# PowerDeliveryBoard.net
KiCad netlist of a schematic drawn in EAGLE
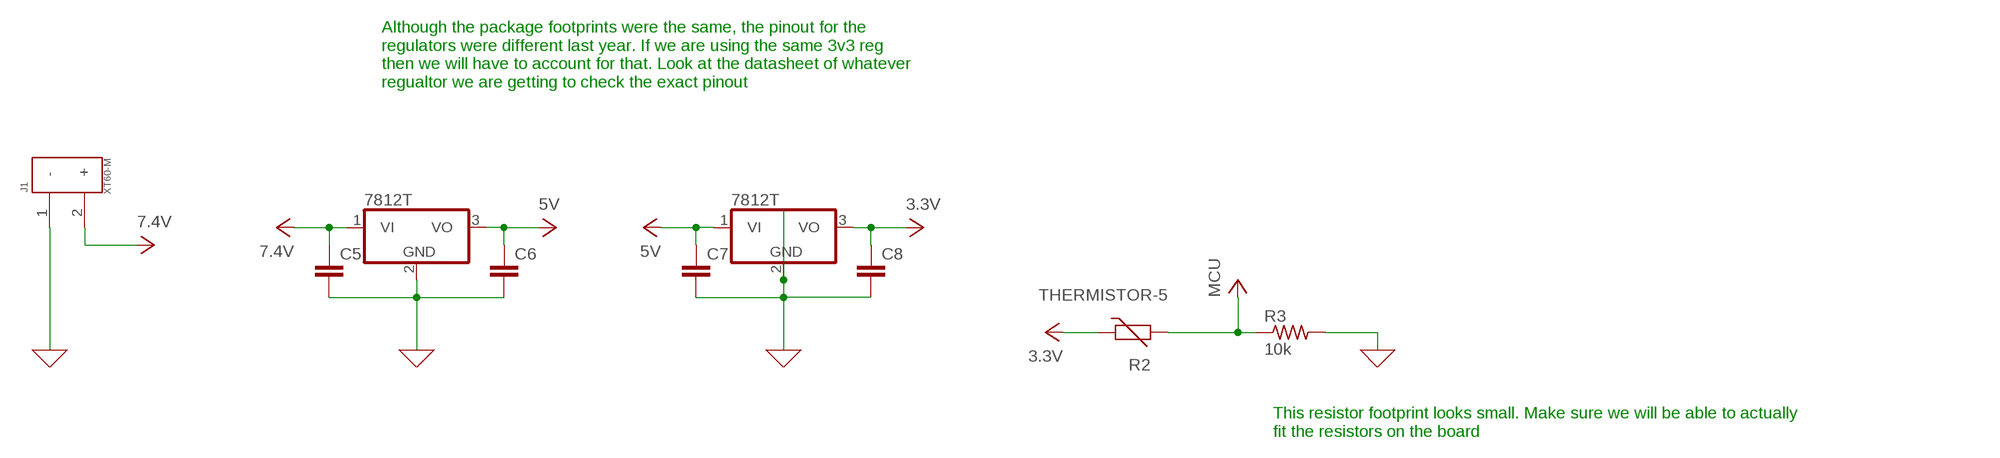
[diagram p0: schematic, sheet 1]

(export (version "E")
  (design (tool "Eeschema 10.0.6"))
  (components
    (comp (ref "C5")
      (value "C2,5-3")
      (footprint "eagle-import:C2.5-3")
      (libsource (lib "eagle-import") (part "C2,5-3"))
    )
    (comp (ref "C6")
      (value "C2,5-3")
      (footprint "eagle-import:C2.5-3")
      (libsource (lib "eagle-import") (part "C2,5-3"))
    )
    (comp (ref "C7")
      (value "C2,5-3")
      (footprint "eagle-import:C2.5-3")
      (libsource (lib "eagle-import") (part "C2,5-3"))
    )
    (comp (ref "C8")
      (value "C2,5-3")
      (footprint "eagle-import:C2.5-3")
      (libsource (lib "eagle-import") (part "C2,5-3"))
    )
    (comp (ref "IC1")
      (value "7812T")
      (footprint "eagle-import:TO220H")
      (libsource (lib "eagle-import") (part "78T12"))
    )
    (comp (ref "IC2")
      (value "7812T")
      (footprint "eagle-import:TO220H")
      (libsource (lib "eagle-import") (part "78T12"))
    )
    (comp (ref "J1")
      (value "XT60-M")
      (footprint "eagle-import:AMASS_XT60-M")
      (fields (field (name "MF") "AMASS"))
      (libsource (lib "eagle-import") (part "XT60-M"))
    )
    (comp (ref "R2")
      (value "THERMISTOR-5")
      (footprint "eagle-import:R-5")
      (libsource (lib "eagle-import") (part "THERMISTOR-5"))
    )
    (comp (ref "R3")
      (value "10k")
      (footprint "eagle-import:0204V")
      (libsource (lib "eagle-import") (part "R-US_0204/2V"))
    )
  )
  (nets
    (net (code "1") (name "3.3V") (class "Default")
      (node (ref "C5") (pin "1") (pinfunction "1_1") (pintype "passive"))
      (node (ref "C6") (pin "1") (pinfunction "1_1") (pintype "passive"))
      (node (ref "C7") (pin "1") (pinfunction "1_1") (pintype "passive"))
      (node (ref "C8") (pin "1") (pinfunction "1_1") (pintype "passive"))
      (node (ref "IC1") (pin "1") (pinfunction "VI_1") (pintype "input"))
      (node (ref "IC1") (pin "3") (pinfunction "VO_3") (pintype "passive"))
      (node (ref "IC2") (pin "1") (pinfunction "VI_1") (pintype "input"))
      (node (ref "IC2") (pin "3") (pinfunction "VO_3") (pintype "passive"))
      (node (ref "J1") (pin "2") (pinfunction "+_2") (pintype "passive"))
      (node (ref "R2") (pin "1") (pinfunction "1_1") (pintype "passive"))
      (node (ref "R2") (pin "2") (pinfunction "2_2") (pintype "passive"))
      (node (ref "R3") (pin "1") (pinfunction "1_1") (pintype "passive"))
    )
    (net (code "2") (name "GND") (class "Default")
      (node (ref "C5") (pin "2") (pinfunction "2_2") (pintype "passive"))
      (node (ref "C6") (pin "2") (pinfunction "2_2") (pintype "passive"))
      (node (ref "C7") (pin "2") (pinfunction "2_2") (pintype "passive"))
      (node (ref "C8") (pin "2") (pinfunction "2_2") (pintype "passive"))
      (node (ref "IC1") (pin "2") (pinfunction "GND_2") (pintype "passive"))
      (node (ref "IC2") (pin "2") (pinfunction "GND_2") (pintype "passive"))
      (node (ref "J1") (pin "1") (pinfunction "-_1") (pintype "passive"))
      (node (ref "R3") (pin "2") (pinfunction "2_2") (pintype "passive"))
    )
  )
)
